# 2025-07-08.net
KiCad netlist of a schematic drawn in EasyEDA Pro
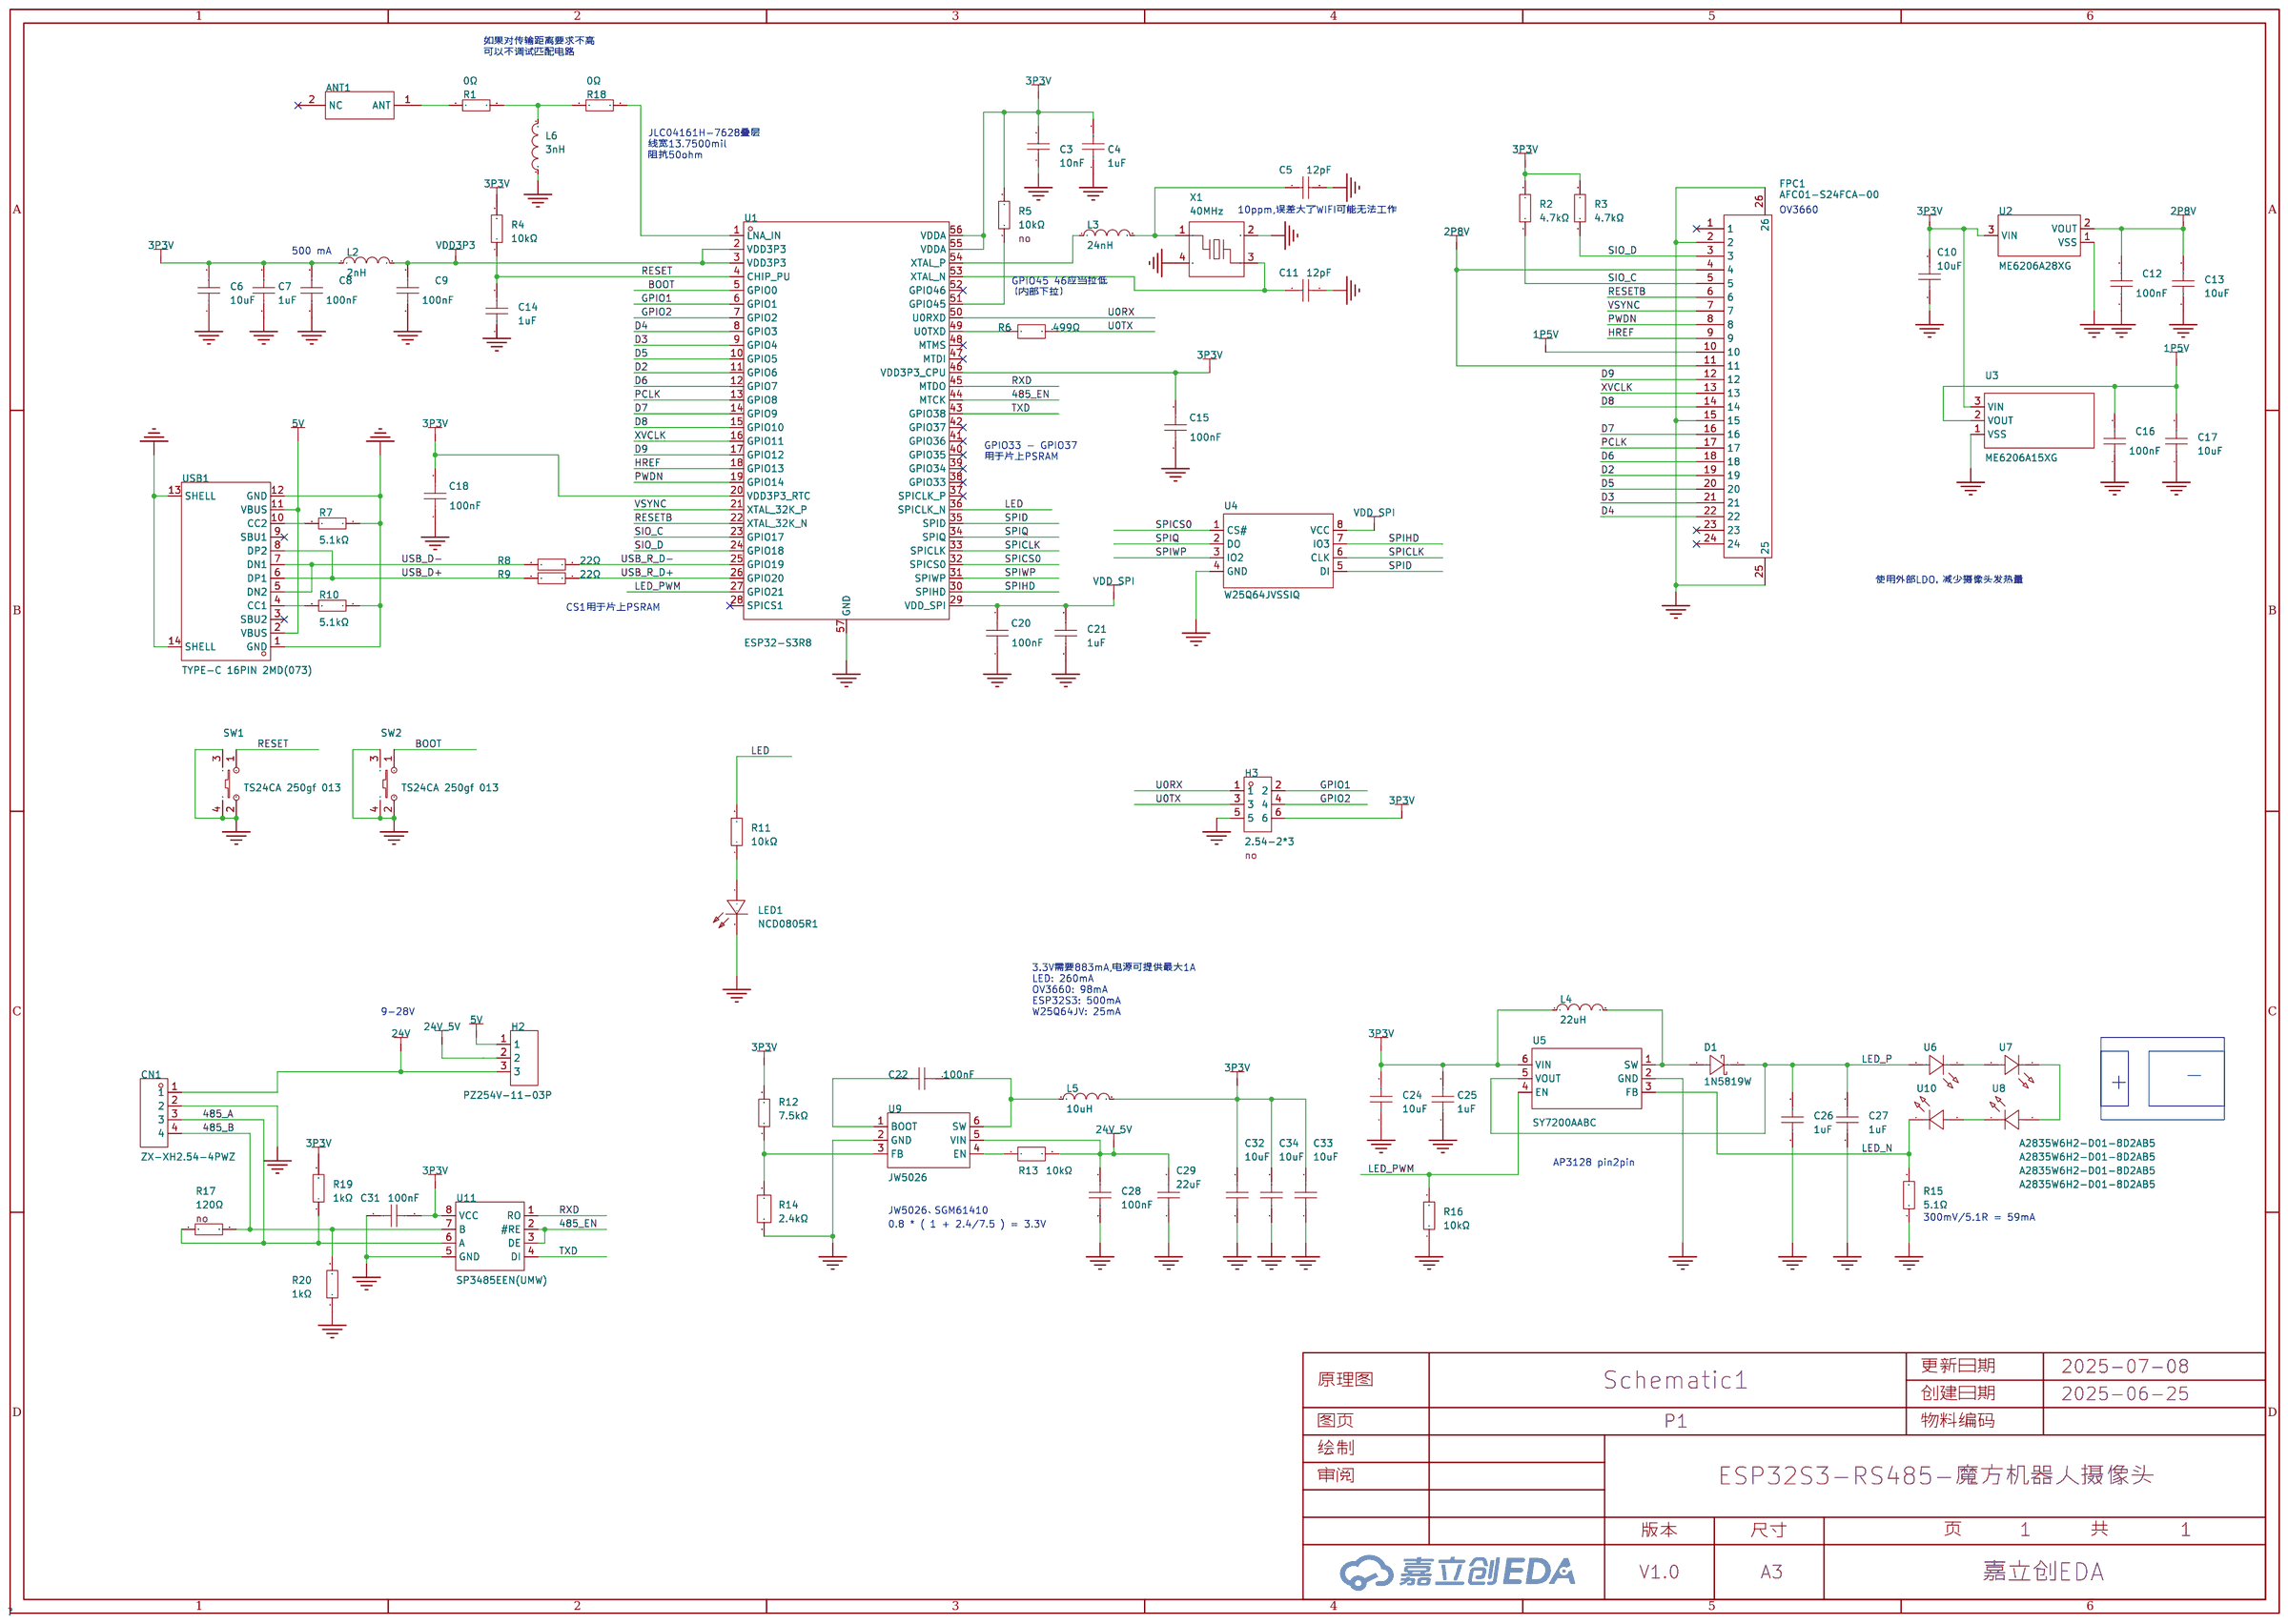
[diagram p0: schematic sheet]

(export (version "E")
  (design (tool "Eeschema 10.0.6"))
  (components
    (comp (ref "ANT1")
      (value "~")
      (footprint "easyedapro:CA-C03")
      (libsource (lib "easyedapro") (part "CA-C03"))
    )
    (comp (ref "C3")
      (value "10nF")
      (footprint "easyedapro:C0603")
      (description "容值:10nF;精度:±10%;额定电压:50V;温度系数:X7R;")
      (fields (field (name "Manufacturer Part") "0603B103K500NT") (field (name "Manufacturer") "FH(风华)"))
      (libsource (lib "easyedapro") (part "0603B103K500NT"))
    )
    (comp (ref "C4")
      (value "1uF")
      (footprint "easyedapro:C0603")
      (description "容值:1uF;精度:±10%;额定电压:50V;材质(温度系数):X5R;")
      (fields
        (field (name "Manufacturer Part") "CL10A105KB8NNNC")
        (field (name "Manufacturer") "SAMSUNG(三星)")
      )
      (libsource (lib "easyedapro") (part "CL10A105KB8NNNC"))
    )
    (comp (ref "C5")
      (value "12pF")
      (footprint "easyedapro:C0603")
      (description "容值:12pF;精度:±5%;额定电压:50V;材质(温度系数):C0G;")
      (fields
        (field (name "Manufacturer Part") "CL10C120JB8NNNC")
        (field (name "Manufacturer") "SAMSUNG(三星)")
      )
      (libsource (lib "easyedapro") (part "CL10C120JB8NNNC"))
    )
    (comp (ref "C6")
      (value "10uF")
      (footprint "easyedapro:C0603")
      (description "容值:10uF;精度:±10%;额定电压:10V;材质(温度系数):X5R;")
      (fields
        (field (name "Manufacturer Part") "CL10A106KP8NNNC")
        (field (name "Manufacturer") "SAMSUNG(三星)")
      )
      (libsource (lib "easyedapro") (part "CL10A106KP8NNNC"))
    )
    (comp (ref "C7")
      (value "1uF")
      (footprint "easyedapro:C0603")
      (description "容值:1uF;精度:±10%;额定电压:50V;材质(温度系数):X5R;")
      (fields
        (field (name "Manufacturer Part") "CL10A105KB8NNNC")
        (field (name "Manufacturer") "SAMSUNG(三星)")
      )
      (libsource (lib "easyedapro") (part "CL10A105KB8NNNC"))
    )
    (comp (ref "C8")
      (value "100nF")
      (footprint "easyedapro:C0603")
      (description "容值:100nF;精度:±10%;额定电压:50V;材质(温度系数):X7R;")
      (fields
        (field (name "Manufacturer Part") "CC0603KRX7R9BB104")
        (field (name "Manufacturer") "YAGEO(国巨)")
      )
      (libsource (lib "easyedapro") (part "CC0603KRX7R9BB104"))
    )
    (comp (ref "C9")
      (value "100nF")
      (footprint "easyedapro:C0603")
      (description "容值:100nF;精度:±10%;额定电压:50V;材质(温度系数):X7R;")
      (fields
        (field (name "Manufacturer Part") "CC0603KRX7R9BB104")
        (field (name "Manufacturer") "YAGEO(国巨)")
      )
      (libsource (lib "easyedapro") (part "CC0603KRX7R9BB104"))
    )
    (comp (ref "C10")
      (value "10uF")
      (footprint "easyedapro:C0603")
      (description "容值:10uF;精度:±10%;额定电压:10V;材质(温度系数):X5R;")
      (fields
        (field (name "Manufacturer Part") "CL10A106KP8NNNC")
        (field (name "Manufacturer") "SAMSUNG(三星)")
      )
      (libsource (lib "easyedapro") (part "CL10A106KP8NNNC"))
    )
    (comp (ref "C11")
      (value "12pF")
      (footprint "easyedapro:C0603")
      (description "容值:12pF;精度:±5%;额定电压:50V;材质(温度系数):C0G;")
      (fields
        (field (name "Manufacturer Part") "CL10C120JB8NNNC")
        (field (name "Manufacturer") "SAMSUNG(三星)")
      )
      (libsource (lib "easyedapro") (part "CL10C120JB8NNNC"))
    )
    (comp (ref "C12")
      (value "100nF")
      (footprint "easyedapro:C0603")
      (description "容值:100nF;精度:±10%;额定电压:50V;材质(温度系数):X7R;")
      (fields
        (field (name "Manufacturer Part") "CC0603KRX7R9BB104")
        (field (name "Manufacturer") "YAGEO(国巨)")
      )
      (libsource (lib "easyedapro") (part "CC0603KRX7R9BB104"))
    )
    (comp (ref "C13")
      (value "10uF")
      (footprint "easyedapro:C0603")
      (description "容值:10uF;精度:±10%;额定电压:10V;材质(温度系数):X5R;")
      (fields
        (field (name "Manufacturer Part") "CL10A106KP8NNNC")
        (field (name "Manufacturer") "SAMSUNG(三星)")
      )
      (libsource (lib "easyedapro") (part "CL10A106KP8NNNC"))
    )
    (comp (ref "C14")
      (value "1uF")
      (footprint "easyedapro:C0603")
      (description "容值:1uF;精度:±10%;额定电压:50V;材质(温度系数):X5R;")
      (fields
        (field (name "Manufacturer Part") "CL10A105KB8NNNC")
        (field (name "Manufacturer") "SAMSUNG(三星)")
      )
      (libsource (lib "easyedapro") (part "CL10A105KB8NNNC"))
    )
    (comp (ref "C15")
      (value "100nF")
      (footprint "easyedapro:C0603")
      (description "容值:100nF;精度:±10%;额定电压:50V;材质(温度系数):X7R;")
      (fields
        (field (name "Manufacturer Part") "CC0603KRX7R9BB104")
        (field (name "Manufacturer") "YAGEO(国巨)")
      )
      (libsource (lib "easyedapro") (part "CC0603KRX7R9BB104"))
    )
    (comp (ref "C16")
      (value "100nF")
      (footprint "easyedapro:C0603")
      (description "容值:100nF;精度:±10%;额定电压:50V;材质(温度系数):X7R;")
      (fields
        (field (name "Manufacturer Part") "CC0603KRX7R9BB104")
        (field (name "Manufacturer") "YAGEO(国巨)")
      )
      (libsource (lib "easyedapro") (part "CC0603KRX7R9BB104"))
    )
    (comp (ref "C17")
      (value "10uF")
      (footprint "easyedapro:C0603")
      (description "容值:10uF;精度:±10%;额定电压:10V;材质(温度系数):X5R;")
      (fields
        (field (name "Manufacturer Part") "CL10A106KP8NNNC")
        (field (name "Manufacturer") "SAMSUNG(三星)")
      )
      (libsource (lib "easyedapro") (part "CL10A106KP8NNNC"))
    )
    (comp (ref "C18")
      (value "100nF")
      (footprint "easyedapro:C0603")
      (description "容值:100nF;精度:±10%;额定电压:50V;材质(温度系数):X7R;")
      (fields
        (field (name "Manufacturer Part") "CC0603KRX7R9BB104")
        (field (name "Manufacturer") "YAGEO(国巨)")
      )
      (libsource (lib "easyedapro") (part "CC0603KRX7R9BB104"))
    )
    (comp (ref "C20")
      (value "100nF")
      (footprint "easyedapro:C0603")
      (description "容值:100nF;精度:±10%;额定电压:50V;材质(温度系数):X7R;")
      (fields
        (field (name "Manufacturer Part") "CC0603KRX7R9BB104")
        (field (name "Manufacturer") "YAGEO(国巨)")
      )
      (libsource (lib "easyedapro") (part "CC0603KRX7R9BB104"))
    )
    (comp (ref "C21")
      (value "1uF")
      (footprint "easyedapro:C0603")
      (description "容值:1uF;精度:±10%;额定电压:50V;材质(温度系数):X5R;")
      (fields
        (field (name "Manufacturer Part") "CL10A105KB8NNNC")
        (field (name "Manufacturer") "SAMSUNG(三星)")
      )
      (libsource (lib "easyedapro") (part "CL10A105KB8NNNC"))
    )
    (comp (ref "C22")
      (value "100nF")
      (footprint "easyedapro:C0603")
      (description "容值:100nF;精度:±10%;额定电压:50V;材质(温度系数):X7R;")
      (fields
        (field (name "Manufacturer Part") "CC0603KRX7R9BB104")
        (field (name "Manufacturer") "YAGEO(国巨)")
      )
      (libsource (lib "easyedapro") (part "CC0603KRX7R9BB104"))
    )
    (comp (ref "C24")
      (value "10uF")
      (footprint "easyedapro:C0603")
      (description "容值:10uF;精度:±10%;额定电压:10V;材质(温度系数):X5R;")
      (fields
        (field (name "Manufacturer Part") "CL10A106KP8NNNC")
        (field (name "Manufacturer") "SAMSUNG(三星)")
      )
      (libsource (lib "easyedapro") (part "CL10A106KP8NNNC"))
    )
    (comp (ref "C25")
      (value "1uF")
      (footprint "easyedapro:C0603")
      (description "容值:1uF;精度:±10%;额定电压:50V;材质(温度系数):X5R;")
      (fields
        (field (name "Manufacturer Part") "CL10A105KB8NNNC")
        (field (name "Manufacturer") "SAMSUNG(三星)")
      )
      (libsource (lib "easyedapro") (part "CL10A105KB8NNNC"))
    )
    (comp (ref "C26")
      (value "1uF")
      (footprint "easyedapro:C0603")
      (description "容值:1uF;精度:±10%;额定电压:50V;材质(温度系数):X5R;")
      (fields
        (field (name "Manufacturer Part") "CL10A105KB8NNNC")
        (field (name "Manufacturer") "SAMSUNG(三星)")
      )
      (libsource (lib "easyedapro") (part "CL10A105KB8NNNC"))
    )
    (comp (ref "C27")
      (value "1uF")
      (footprint "easyedapro:C0603")
      (description "容值:1uF;精度:±10%;额定电压:50V;材质(温度系数):X5R;")
      (fields
        (field (name "Manufacturer Part") "CL10A105KB8NNNC")
        (field (name "Manufacturer") "SAMSUNG(三星)")
      )
      (libsource (lib "easyedapro") (part "CL10A105KB8NNNC"))
    )
    (comp (ref "C28")
      (value "100nF")
      (footprint "easyedapro:C0603")
      (description "容值:100nF;精度:±10%;额定电压:50V;材质(温度系数):X7R;")
      (fields
        (field (name "Manufacturer Part") "CC0603KRX7R9BB104")
        (field (name "Manufacturer") "YAGEO(国巨)")
      )
      (libsource (lib "easyedapro") (part "CC0603KRX7R9BB104"))
    )
    (comp (ref "C29")
      (value "22uF")
      (footprint "easyedapro:C0805")
      (description "容值:22uF;精度:±20%;额定电压:35V;材质(温度系数):X5R;")
      (fields
        (field (name "Manufacturer Part") "CGA0805X5R226M350MT")
        (field (name "Manufacturer") "HRE(芯声)")
      )
      (libsource (lib "easyedapro") (part "CGA0805X5R226M350MT"))
    )
    (comp (ref "C31")
      (value "100nF")
      (footprint "easyedapro:C0603")
      (description "容值:100nF;精度:±10%;额定电压:50V;材质(温度系数):X7R;")
      (fields
        (field (name "Manufacturer Part") "CC0603KRX7R9BB104")
        (field (name "Manufacturer") "YAGEO(国巨)")
      )
      (libsource (lib "easyedapro") (part "CC0603KRX7R9BB104"))
    )
    (comp (ref "C32")
      (value "10uF")
      (footprint "easyedapro:C0603")
      (description "容值:10uF;精度:±10%;额定电压:10V;材质(温度系数):X5R;")
      (fields
        (field (name "Manufacturer Part") "CL10A106KP8NNNC")
        (field (name "Manufacturer") "SAMSUNG(三星)")
      )
      (libsource (lib "easyedapro") (part "CL10A106KP8NNNC"))
    )
    (comp (ref "C33")
      (value "10uF")
      (footprint "easyedapro:C0603")
      (description "容值:10uF;精度:±10%;额定电压:10V;材质(温度系数):X5R;")
      (fields
        (field (name "Manufacturer Part") "CL10A106KP8NNNC")
        (field (name "Manufacturer") "SAMSUNG(三星)")
      )
      (libsource (lib "easyedapro") (part "CL10A106KP8NNNC"))
    )
    (comp (ref "C34")
      (value "10uF")
      (footprint "easyedapro:C0603")
      (description "容值:10uF;精度:±10%;额定电压:10V;材质(温度系数):X5R;")
      (fields
        (field (name "Manufacturer Part") "CL10A106KP8NNNC")
        (field (name "Manufacturer") "SAMSUNG(三星)")
      )
      (libsource (lib "easyedapro") (part "CL10A106KP8NNNC"))
    )
    (comp (ref "CN1")
      (value "ZX-XH2.54-4PWZ")
      (footprint "easyedapro:CONN-TH_4P-P2.50_ZX-XH2.54-4PWZ")
      (fields (field (name "Manufacturer") "Megastar(兆星)"))
      (libsource (lib "easyedapro") (part "ZX-XH2.54-4PWZ"))
    )
    (comp (ref "D1")
      (value "1N5819W")
      (footprint "easyedapro:SOD-123_L2.7-W1.6-LS3.7-RD")
      (description "二极管配置:独立式;正向压降(Vf):600mV@200mA;直流反向耐压(Vr):40V;整流电流:350mA;")
      (fields (field (name "Manufacturer") "JSMSEMI(杰盛微)"))
      (libsource (lib "easyedapro") (part "1N5819W_C963381"))
    )
    (comp (ref "FPC1")
      (value "AFC01-S24FCA-00")
      (footprint "easyedapro:FPC-SMD_24P-P0.50_AFC01-S24FCA-00")
      (description "锁定特性:翻盖式;触点类型:下接;触点数量:24P;间距:0.5mm;安装类型:卧贴;")
      (fields (field (name "Manufacturer") "JS(钜硕电子)"))
      (libsource (lib "easyedapro") (part "AFC01-S24FCA-00"))
    )
    (comp (ref "H2")
      (value "PZ254V-11-03P")
      (footprint "easyedapro:HDR-TH_3P-P2.54-V-M")
      (fields (field (name "Manufacturer") "XFCN(兴飞)"))
      (libsource (lib "easyedapro") (part "PZ254V-11-03P_C2937625"))
    )
    (comp (ref "H3")
      (value "2.54-2*3")
      (footprint "easyedapro:HDR-TH_6P-P2.54-V-R2-C3-S2.54_A2541WV-2X3P")
      (description "插针结构:2x3P;间距:2.54mm;排数:双排;总PIN位数:6P;")
      (fields (field (name "Manufacturer") "ZHOURI(洲日)") (field (name "Add into BOM") "no"))
      (libsource (lib "easyedapro") (part "2.54-2*3"))
    )
    (comp (ref "L2")
      (value "2nH")
      (footprint "easyedapro:L0603")
      (description "电感值:2nH;额定电流:-;饱和电流(Isat):-;直流电阻(DCR):-;")
      (fields
        (field (name "Manufacturer Part") "SDCL1608C2N0STDF")
        (field (name "Manufacturer") "Sunlord(顺络)")
      )
      (libsource (lib "easyedapro") (part "SDCL1608C2N0STDF_C370234"))
    )
    (comp (ref "L3")
      (value "24nH")
      (footprint "easyedapro:IND-SMD_L1.6-W0.8")
      (description "电感值:24nH;精度:±2%;额定电流:500mA;饱和电流(Isat):-;")
      (fields (field (name "Manufacturer Part") "LQW18AN24NG00D") (field (name "Manufacturer") "muRata(村田)"))
      (libsource (lib "easyedapro") (part "LQW18AN24NG00D"))
    )
    (comp (ref "L4")
      (value "22uH")
      (footprint "easyedapro:IND-SMD_L4.0-W4.0")
      (description "电感值:22uH;精度:±20%;额定电流:1.1A;饱和电流(Isat):1.5A;")
      (fields
        (field (name "Manufacturer Part") "FHD4020S-220MT")
        (field (name "Manufacturer") "cjiang(长江微电)")
      )
      (libsource (lib "easyedapro") (part "FHD4020S-220MT"))
    )
    (comp (ref "L5")
      (value "10uH")
      (footprint "easyedapro:IND-SMD_L4.0-W4.0")
      (description "电感值:22uH;精度:±20%;额定电流:1.1A;饱和电流(Isat):1.5A;")
      (fields (field (name "Manufacturer Part") "FNR4030S100MT") (field (name "Manufacturer") "cjiang(长江微电)"))
      (libsource (lib "easyedapro") (part "FHD4020S-220MT"))
    )
    (comp (ref "L6")
      (value "3nH")
      (footprint "easyedapro:L0402")
      (description "电感值:3nH;精度:-;额定电流:800mA;饱和电流(Isat):-;直流电阻(DCR):125mΩ;")
      (fields (field (name "Manufacturer Part") "LQG15HS3N0S02D") (field (name "Manufacturer") "muRata(村田)"))
      (libsource (lib "easyedapro") (part "LQG15HS3N0S02D"))
    )
    (comp (ref "LED1")
      (value "NCD0805R1")
      (footprint "easyedapro:LED0805-R-RD")
      (fields (field (name "Manufacturer") "国星光电"))
      (libsource (lib "easyedapro") (part "FC-2012HRK-620D"))
    )
    (comp (ref "R1")
      (value "0Ω")
      (footprint "easyedapro:R0402")
      (description "电阻类型:厚膜电阻;阻值:0Ω;精度:±1%;功率:62.5mW;最大工作电压:50V;温度系数:±800ppm/°C;")
      (fields
        (field (name "Manufacturer Part") "0402WGF0000TCE")
        (field (name "Manufacturer") "UNI-ROYAL(厚声)")
      )
      (libsource (lib "easyedapro") (part "0402WGF0000TCE"))
    )
    (comp (ref "R2")
      (value "4.7kΩ")
      (footprint "easyedapro:R0603")
      (description "电阻类型:厚膜电阻;阻值:4.7kΩ;精度:±1%;功率:100mW;最大工作电压:75V;温度系数:±100ppm/°C;")
      (fields
        (field (name "Manufacturer Part") "0603WAF4701T5E")
        (field (name "Manufacturer") "UNI-ROYAL(厚声)")
      )
      (libsource (lib "easyedapro") (part "0603WAF4701T5E"))
    )
    (comp (ref "R3")
      (value "4.7kΩ")
      (footprint "easyedapro:R0603")
      (description "电阻类型:厚膜电阻;阻值:4.7kΩ;精度:±1%;功率:100mW;最大工作电压:75V;温度系数:±100ppm/°C;")
      (fields
        (field (name "Manufacturer Part") "0603WAF4701T5E")
        (field (name "Manufacturer") "UNI-ROYAL(厚声)")
      )
      (libsource (lib "easyedapro") (part "0603WAF4701T5E"))
    )
    (comp (ref "R4")
      (value "10kΩ")
      (footprint "easyedapro:R0603")
      (description "电阻类型:厚膜电阻;阻值:10kΩ;精度:±1%;功率:100mW;工作电压:75V;温度系数:±100ppm/°C;")
      (fields
        (field (name "Manufacturer Part") "0603WAF1002T5E")
        (field (name "Manufacturer") "UNI-ROYAL(厚声)")
      )
      (libsource (lib "easyedapro") (part "0603WAF1002T5E"))
    )
    (comp (ref "R5")
      (value "10kΩ")
      (footprint "easyedapro:R0603")
      (description "电阻类型:厚膜电阻;阻值:10kΩ;精度:±1%;功率:100mW;工作电压:75V;温度系数:±100ppm/°C;")
      (fields
        (field (name "Manufacturer Part") "0603WAF1002T5E")
        (field (name "Manufacturer") "UNI-ROYAL(厚声)")
        (field (name "Add into BOM") "no")
      )
      (libsource (lib "easyedapro") (part "0603WAF1002T5E"))
    )
    (comp (ref "R6")
      (value "499Ω")
      (footprint "easyedapro:R0603")
      (description "电阻类型:厚膜电阻;阻值:499Ω;精度:±1%;功率:100mW;工作电压:75V;温度系数:±100ppm/°C;")
      (fields (field (name "Manufacturer Part") "FRC0603F4990TS") (field (name "Manufacturer") "FOJAN(富捷)"))
      (libsource (lib "easyedapro") (part "FRC0603F4990TS"))
    )
    (comp (ref "R7")
      (value "5.1kΩ")
      (footprint "easyedapro:R0603")
      (description "阻值:5.1kΩ;精度:±1%;功率:100mW;温度系数:±100ppm/°C;电阻类型:厚膜电阻;")
      (fields
        (field (name "Manufacturer Part") "0603WAF5101T5E")
        (field (name "Manufacturer") "UNI-ROYAL(厚声)")
      )
      (libsource (lib "easyedapro") (part "0603WAF5101T5E"))
    )
    (comp (ref "R8")
      (value "22Ω")
      (footprint "easyedapro:R0603")
      (description "电阻类型:厚膜电阻;阻值:0Ω;精度:±1%;功率:100mW;最大工作电压:75V;")
      (fields
        (field (name "Manufacturer Part") "0603WAF220JT5E")
        (field (name "Manufacturer") "UNI-ROYAL(厚声)")
      )
      (libsource (lib "easyedapro") (part "0603WAF0000T5E"))
    )
    (comp (ref "R9")
      (value "22Ω")
      (footprint "easyedapro:R0603")
      (description "电阻类型:厚膜电阻;阻值:0Ω;精度:±1%;功率:100mW;最大工作电压:75V;")
      (fields
        (field (name "Manufacturer Part") "0603WAF220JT5E")
        (field (name "Manufacturer") "UNI-ROYAL(厚声)")
      )
      (libsource (lib "easyedapro") (part "0603WAF0000T5E"))
    )
    (comp (ref "R10")
      (value "5.1kΩ")
      (footprint "easyedapro:R0603")
      (description "阻值:5.1kΩ;精度:±1%;功率:100mW;温度系数:±100ppm/°C;电阻类型:厚膜电阻;")
      (fields
        (field (name "Manufacturer Part") "0603WAF5101T5E")
        (field (name "Manufacturer") "UNI-ROYAL(厚声)")
      )
      (libsource (lib "easyedapro") (part "0603WAF5101T5E"))
    )
    (comp (ref "R11")
      (value "10kΩ")
      (footprint "easyedapro:R0603")
      (description "电阻类型:厚膜电阻;阻值:10kΩ;精度:±1%;功率:100mW;工作电压:75V;温度系数:±100ppm/°C;")
      (fields
        (field (name "Manufacturer Part") "0603WAF1002T5E")
        (field (name "Manufacturer") "UNI-ROYAL(厚声)")
      )
      (libsource (lib "easyedapro") (part "0603WAF1002T5E"))
    )
    (comp (ref "R12")
      (value "7.5kΩ")
      (fields
        (field (name "Manufacturer Part") "0603WAF7501T5E")
        (field (name "Manufacturer") "UNI-ROYAL(厚声)")
      )
      (libsource (lib "easyedapro") (part "0603waf4702t5e"))
    )
    (comp (ref "R13")
      (value "10kΩ")
      (footprint "easyedapro:R0603")
      (description "电阻类型:薄膜电阻;阻值:10kΩ;精度:±0.1%;功率:100mW;")
      (fields (field (name "Manufacturer Part") "AT0603BRD0710KL") (field (name "Manufacturer") "YAGEO(国巨)"))
      (libsource (lib "easyedapro") (part "AT0603BRD0710KL"))
    )
    (comp (ref "R14")
      (value "2.4kΩ")
      (fields (field (name "Manufacturer Part") "FRC0603F2401TS") (field (name "Manufacturer") "FOJAN(富捷)"))
      (libsource (lib "easyedapro") (part "FRC0603F1502TS"))
    )
    (comp (ref "R15")
      (value "5.1Ω")
      (footprint "easyedapro:R0603")
      (description "电阻类型:厚膜电阻;阻值:5.1Ω;精度:±1%;功率:100mW;最大工作电压:75V;温度系数:±200ppm/°C;")
      (fields
        (field (name "Manufacturer Part") "0603WAF510KT5E")
        (field (name "Manufacturer") "UNI-ROYAL(厚声)")
      )
      (libsource (lib "easyedapro") (part "0603WAF510KT5E"))
    )
    (comp (ref "R16")
      (value "10kΩ")
      (footprint "easyedapro:R0603")
      (description "电阻类型:厚膜电阻;阻值:10kΩ;精度:±1%;功率:100mW;工作电压:75V;温度系数:±100ppm/°C;")
      (fields
        (field (name "Manufacturer Part") "0603WAF1002T5E")
        (field (name "Manufacturer") "UNI-ROYAL(厚声)")
      )
      (libsource (lib "easyedapro") (part "0603WAF1002T5E"))
    )
    (comp (ref "R17")
      (value "120Ω")
      (footprint "easyedapro:R0603")
      (description "电阻类型:厚膜电阻;阻值:120Ω;精度:±1%;功率:100mW;最大工作电压:75V;温度系数:±100ppm/°C;")
      (fields
        (field (name "Manufacturer Part") "0603WAF1200T5E")
        (field (name "Manufacturer") "UNI-ROYAL(厚声)")
        (field (name "Add into BOM") "no")
      )
      (libsource (lib "easyedapro") (part "0603WAF1200T5E"))
    )
    (comp (ref "R18")
      (value "0Ω")
      (footprint "easyedapro:R0402")
      (description "电阻类型:厚膜电阻;阻值:0Ω;精度:±1%;功率:62.5mW;最大工作电压:50V;温度系数:±800ppm/°C;")
      (fields
        (field (name "Manufacturer Part") "0402WGF0000TCE")
        (field (name "Manufacturer") "UNI-ROYAL(厚声)")
      )
      (libsource (lib "easyedapro") (part "0402WGF0000TCE"))
    )
    (comp (ref "R19")
      (value "1kΩ")
      (footprint "easyedapro:R0603")
      (description "电阻类型:厚膜电阻;阻值:1kΩ;精度:±1%;功率:100mW;最大工作电压:75V;温度系数:±100ppm/°C;")
      (fields
        (field (name "Manufacturer Part") "0603WAF1001T5E")
        (field (name "Manufacturer") "UNI-ROYAL(厚声)")
      )
      (libsource (lib "easyedapro") (part "0603WAF1001T5E"))
    )
    (comp (ref "R20")
      (value "1kΩ")
      (footprint "easyedapro:R0603")
      (description "电阻类型:厚膜电阻;阻值:1kΩ;精度:±1%;功率:100mW;最大工作电压:75V;温度系数:±100ppm/°C;")
      (fields
        (field (name "Manufacturer Part") "0603WAF1001T5E")
        (field (name "Manufacturer") "UNI-ROYAL(厚声)")
      )
      (libsource (lib "easyedapro") (part "0603WAF1001T5E"))
    )
    (comp (ref "SW1")
      (value "TS24CA 250gf 013")
      (footprint "easyedapro:SW-SMD_L4.7-W3.5-P3.35-EH")
      (fields (field (name "Manufacturer") "SHOU HAN(首韩)"))
      (libsource (lib "easyedapro") (part "TS24CA 250GF 013"))
    )
    (comp (ref "SW2")
      (value "TS24CA 250gf 013")
      (footprint "easyedapro:SW-SMD_L4.7-W3.5-P3.35-EH")
      (fields (field (name "Manufacturer") "SHOU HAN(首韩)"))
      (libsource (lib "easyedapro") (part "TS24CA 250GF 013"))
    )
    (comp (ref "U1")
      (value "ESP32-S3R8")
      (footprint "easyedapro:QFN-56_L7.0-W7.0-P0.40-TL-EP4.0")
      (fields (field (name "Manufacturer") "ESPRESSIF(乐鑫)"))
      (libsource (lib "easyedapro") (part "ESP32-S3(R8)"))
    )
    (comp (ref "U2")
      (value "ME6206A28XG")
      (footprint "easyedapro:SOT-23_L2.9-W1.3-P1.90-LS2.4-BR")
      (description "输出类型:固定;工作电压:6V;输出电压:2.8V;输出电流:300mA;电源纹波抑制比(PSRR):50dB@(1kHz);输出极性:正极;")
      (fields (field (name "Manufacturer") "MICRONE(南京微盟)"))
      (libsource (lib "easyedapro") (part "ME6206A28XG"))
    )
    (comp (ref "U3")
      (value "ME6206A15XG")
      (footprint "easyedapro:SOT-23-3_L2.9-W1.6-P1.90-LS2.8-BR")
      (description "输出类型:固定;工作电压:6V;输出电压:1.5V;输出电流:100mA;电源纹波抑制比(PSRR):45dB@(1kHz);输出极性:正极;")
      (fields (field (name "Manufacturer") "MICRONE(南京微盟)"))
      (libsource (lib "easyedapro") (part "ME6206A15XG"))
    )
    (comp (ref "U4")
      (value "W25Q64JVSSIQ")
      (footprint "easyedapro:SOP-8_L5.3-W5.3-P1.27-LS8.0-BL")
      (description "接口类型:SPI;存储容量:-;时钟频率(fc):133MHz;")
      (fields (field (name "Manufacturer") "WINBOND(华邦)"))
      (libsource (lib "easyedapro") (part "W25Q64JVSSIQ"))
    )
    (comp (ref "U5")
      (value "SY7200AABC")
      (footprint "easyedapro:SOT-23-6_L2.9-W1.6-P0.95-LS2.8-BR")
      (description "类型:-;工作电压:2.5V~5.5V;开关频率:-;通道数:-;输出电压:-;调光:-;拓扑结构:升压;")
      (fields (field (name "Manufacturer") "silergy(矽力杰)"))
      (libsource (lib "easyedapro") (part "AP3128AE3036ES6"))
    )
    (comp (ref "U6")
      (value "A2835W6H2-D01-8D2AB5")
      (footprint "easyedapro:LED-SMD_L3.5-W2.8-FD-2835_WHITE")
      (description "发光颜色:白色;正向电压(VF):2.9V~3.3V;正向电流:-;色温:6500K;")
      (fields (field (name "Manufacturer") "HONGLITRONIC(鸿利光电)"))
      (libsource (lib "easyedapro") (part "A2835W6H2-D01-8D2AB5"))
    )
    (comp (ref "U7")
      (value "A2835W6H2-D01-8D2AB5")
      (footprint "easyedapro:LED-SMD_L3.5-W2.8-FD-2835_WHITE")
      (description "发光颜色:白色;正向电压(VF):2.9V~3.3V;正向电流:-;色温:6500K;")
      (fields (field (name "Manufacturer") "HONGLITRONIC(鸿利光电)"))
      (libsource (lib "easyedapro") (part "A2835W6H2-D01-8D2AB5"))
    )
    (comp (ref "U8")
      (value "A2835W6H2-D01-8D2AB5")
      (footprint "easyedapro:LED-SMD_L3.5-W2.8-FD-2835_WHITE")
      (description "发光颜色:白色;正向电压(VF):2.9V~3.3V;正向电流:-;色温:6500K;")
      (fields (field (name "Manufacturer") "HONGLITRONIC(鸿利光电)"))
      (libsource (lib "easyedapro") (part "A2835W6H2-D01-8D2AB5"))
    )
    (comp (ref "U9")
      (value "JW5026")
      (footprint "easyedapro:TSOT-23-6_L2.9-W1.6-P0.95-LS2.8-BL")
      (fields (field (name "Manufacturer") "Joulwatt(杰华特)"))
      (libsource (lib "easyedapro") (part "SGM61410XN6G/TR"))
    )
    (comp (ref "U10")
      (value "A2835W6H2-D01-8D2AB5")
      (footprint "easyedapro:LED-SMD_L3.5-W2.8-FD-2835_WHITE")
      (description "发光颜色:白色;正向电压(VF):2.9V~3.3V;正向电流:-;色温:6500K;")
      (fields (field (name "Manufacturer") "HONGLITRONIC(鸿利光电)"))
      (libsource (lib "easyedapro") (part "A2835W6H2-D01-8D2AB5"))
    )
    (comp (ref "U11")
      (value "SP3485EEN(UMW)")
      (footprint "easyedapro:SOP-8_L5.0-W4.0-P1.27-LS6.0-BL")
      (description "类型:收发器;数据速率:12Mbps;")
      (fields (field (name "Manufacturer") "UMW(友台半导体)"))
      (libsource (lib "easyedapro") (part "SP3485EEN"))
    )
    (comp (ref "USB1")
      (value "TYPE-C 16PIN 2MD(073)")
      (footprint "easyedapro:USB-C-SMD_TYPE-C-6PIN-2MD-073")
      (description "连接器类型:Type-C;标准:-;公母:母;触点数量:16P;端口数量:1;安装方式:卧贴;额定电流 - 电源:5A;工作温度范围:-25°C~+85°C;")
      (fields (field (name "Manufacturer") "SHOU HAN(首韩)"))
      (libsource (lib "easyedapro") (part "TYPE-C 16PIN 2MD(073)"))
    )
    (comp (ref "X1")
      (value "40MHz")
      (footprint "easyedapro:CRYSTAL-SMD_4P-L3.2-W2.5-BL_SIT8008BI")
      (description "晶振类型:贴片晶振;频率:40MHz;常温频差:±10ppm;负载电容:10pF;频率稳定度:±30ppm;")
      (fields (field (name "Manufacturer Part") "CF4040M00010001") (field (name "Manufacturer") "HUAXIN(华昕)"))
      (libsource (lib "easyedapro") (part "CF4040M00010001"))
    )
  )
  (nets
    (net (code "1") (name "/485_A") (class "Default")
      (node (ref "CN1") (pin "3") (pinfunction "3_3") (pintype "unspecified"))
      (node (ref "R17") (pin "1") (pinfunction "1_1") (pintype "input"))
      (node (ref "R19") (pin "1") (pinfunction "1_1") (pintype "input"))
      (node (ref "U11") (pin "6") (pinfunction "A_6") (pintype "unspecified"))
    )
    (net (code "2") (name "/485_B") (class "Default")
      (node (ref "CN1") (pin "4") (pinfunction "4_4") (pintype "unspecified"))
      (node (ref "R17") (pin "2") (pinfunction "2_2") (pintype "input"))
      (node (ref "R20") (pin "2") (pinfunction "2_2") (pintype "input"))
      (node (ref "U11") (pin "7") (pinfunction "B_7") (pintype "unspecified"))
    )
    (net (code "3") (name "/485_EN") (class "Default")
      (node (ref "U1") (pin "44") (pinfunction "MTCK_44") (pintype "unspecified"))
      (node (ref "U11") (pin "2") (pinfunction "#RE_2") (pintype "unspecified"))
      (node (ref "U11") (pin "3") (pinfunction "DE_3") (pintype "unspecified"))
    )
    (net (code "4") (name "/BOOT") (class "Default")
      (node (ref "SW2") (pin "1") (pinfunction "1_1") (pintype "unspecified"))
      (node (ref "U1") (pin "5") (pinfunction "GPIO0_5") (pintype "unspecified"))
    )
    (net (code "5") (name "/D2") (class "Default")
      (node (ref "FPC1") (pin "19") (pinfunction "19_19") (pintype "unspecified"))
      (node (ref "U1") (pin "11") (pinfunction "GPIO6_11") (pintype "unspecified"))
    )
    (net (code "6") (name "/D3") (class "Default")
      (node (ref "FPC1") (pin "21") (pinfunction "21_21") (pintype "unspecified"))
      (node (ref "U1") (pin "9") (pinfunction "GPIO4_9") (pintype "unspecified"))
    )
    (net (code "7") (name "/D4") (class "Default")
      (node (ref "FPC1") (pin "22") (pinfunction "22_22") (pintype "unspecified"))
      (node (ref "U1") (pin "8") (pinfunction "GPIO3_8") (pintype "unspecified"))
    )
    (net (code "8") (name "/D5") (class "Default")
      (node (ref "FPC1") (pin "20") (pinfunction "20_20") (pintype "unspecified"))
      (node (ref "U1") (pin "10") (pinfunction "GPIO5_10") (pintype "unspecified"))
    )
    (net (code "9") (name "/D6") (class "Default")
      (node (ref "FPC1") (pin "18") (pinfunction "18_18") (pintype "unspecified"))
      (node (ref "U1") (pin "12") (pinfunction "GPIO7_12") (pintype "unspecified"))
    )
    (net (code "10") (name "/D7") (class "Default")
      (node (ref "FPC1") (pin "16") (pinfunction "16_16") (pintype "unspecified"))
      (node (ref "U1") (pin "14") (pinfunction "GPIO9_14") (pintype "unspecified"))
    )
    (net (code "11") (name "/D8") (class "Default")
      (node (ref "FPC1") (pin "14") (pinfunction "14_14") (pintype "unspecified"))
      (node (ref "U1") (pin "15") (pinfunction "GPIO10_15") (pintype "unspecified"))
    )
    (net (code "12") (name "/D9") (class "Default")
      (node (ref "FPC1") (pin "12") (pinfunction "12_12") (pintype "unspecified"))
      (node (ref "U1") (pin "17") (pinfunction "GPIO12_17") (pintype "unspecified"))
    )
    (net (code "13") (name "/GPIO1") (class "Default")
      (node (ref "H3") (pin "2") (pinfunction "2_2") (pintype "unspecified"))
      (node (ref "U1") (pin "6") (pinfunction "GPIO1_6") (pintype "unspecified"))
    )
    (net (code "14") (name "/GPIO2") (class "Default")
      (node (ref "H3") (pin "4") (pinfunction "4_4") (pintype "unspecified"))
      (node (ref "U1") (pin "7") (pinfunction "GPIO2_7") (pintype "unspecified"))
    )
    (net (code "15") (name "/HREF") (class "Default")
      (node (ref "FPC1") (pin "9") (pinfunction "9_9") (pintype "unspecified"))
      (node (ref "U1") (pin "18") (pinfunction "GPIO13_18") (pintype "unspecified"))
    )
    (net (code "16") (name "/LED") (class "Default")
      (node (ref "R11") (pin "2") (pinfunction "2_2") (pintype "input"))
      (node (ref "U1") (pin "36") (pinfunction "SPICLK_N_36") (pintype "unspecified"))
    )
    (net (code "17") (name "/LED_N") (class "Default")
      (node (ref "R15") (pin "2") (pinfunction "2_2") (pintype "input"))
      (node (ref "U10") (pin "1") (pinfunction "K_1") (pintype "unspecified"))
      (node (ref "U5") (pin "3") (pinfunction "FB_3") (pintype "unspecified"))
    )
    (net (code "18") (name "/LED_P") (class "Default")
      (node (ref "C26") (pin "2") (pinfunction "2_2") (pintype "unspecified"))
      (node (ref "C27") (pin "2") (pinfunction "2_2") (pintype "unspecified"))
      (node (ref "D1") (pin "1") (pinfunction "C_1") (pintype "unspecified"))
      (node (ref "U5") (pin "5") (pinfunction "VOUT_5") (pintype "unspecified"))
      (node (ref "U6") (pin "2") (pinfunction "A_2") (pintype "unspecified"))
    )
    (net (code "19") (name "/LED_PWM") (class "Default")
      (node (ref "R16") (pin "2") (pinfunction "2_2") (pintype "input"))
      (node (ref "U1") (pin "27") (pinfunction "GPIO21_27") (pintype "unspecified"))
      (node (ref "U5") (pin "4") (pinfunction "EN_4") (pintype "unspecified"))
    )
    (net (code "20") (name "/PCLK") (class "Default")
      (node (ref "FPC1") (pin "17") (pinfunction "17_17") (pintype "unspecified"))
      (node (ref "U1") (pin "13") (pinfunction "GPIO8_13") (pintype "unspecified"))
    )
    (net (code "21") (name "/PWDN") (class "Default")
      (node (ref "FPC1") (pin "8") (pinfunction "8_8") (pintype "unspecified"))
      (node (ref "U1") (pin "19") (pinfunction "GPIO14_19") (pintype "unspecified"))
    )
    (net (code "22") (name "/RESET") (class "Default")
      (node (ref "C14") (pin "2") (pinfunction "2_2") (pintype "unspecified"))
      (node (ref "R4") (pin "1") (pinfunction "1_1") (pintype "input"))
      (node (ref "SW1") (pin "1") (pinfunction "1_1") (pintype "unspecified"))
      (node (ref "U1") (pin "4") (pinfunction "CHIP_PU_4") (pintype "unspecified"))
    )
    (net (code "23") (name "/RESETB") (class "Default")
      (node (ref "FPC1") (pin "6") (pinfunction "6_6") (pintype "unspecified"))
      (node (ref "U1") (pin "22") (pinfunction "XTAL_32K_N_22") (pintype "unspecified"))
    )
    (net (code "24") (name "/RXD") (class "Default")
      (node (ref "U1") (pin "45") (pinfunction "MTDO_45") (pintype "unspecified"))
      (node (ref "U11") (pin "1") (pinfunction "RO_1") (pintype "unspecified"))
    )
    (net (code "25") (name "/SIO_C") (class "Default")
      (node (ref "FPC1") (pin "5") (pinfunction "5_5") (pintype "unspecified"))
      (node (ref "R2") (pin "1") (pinfunction "1_1") (pintype "input"))
      (node (ref "U1") (pin "23") (pinfunction "GPIO17_23") (pintype "unspecified"))
    )
    (net (code "26") (name "/SIO_D") (class "Default")
      (node (ref "FPC1") (pin "3") (pinfunction "3_3") (pintype "unspecified"))
      (node (ref "R3") (pin "1") (pinfunction "1_1") (pintype "input"))
      (node (ref "U1") (pin "24") (pinfunction "GPIO18_24") (pintype "unspecified"))
    )
    (net (code "27") (name "/SPICLK") (class "Default")
      (node (ref "U1") (pin "33") (pinfunction "SPICLK_33") (pintype "unspecified"))
      (node (ref "U4") (pin "6") (pinfunction "CLK_6") (pintype "unspecified"))
    )
    (net (code "28") (name "/SPICS0") (class "Default")
      (node (ref "U1") (pin "32") (pinfunction "SPICS0_32") (pintype "unspecified"))
      (node (ref "U4") (pin "1") (pinfunction "CS#_1") (pintype "unspecified"))
    )
    (net (code "29") (name "/SPID") (class "Default")
      (node (ref "U1") (pin "35") (pinfunction "SPID_35") (pintype "unspecified"))
      (node (ref "U4") (pin "5") (pinfunction "DI_5") (pintype "unspecified"))
    )
    (net (code "30") (name "/SPIHD") (class "Default")
      (node (ref "U1") (pin "30") (pinfunction "SPIHD_30") (pintype "unspecified"))
      (node (ref "U4") (pin "7") (pinfunction "IO3_7") (pintype "unspecified"))
    )
    (net (code "31") (name "/SPIQ") (class "Default")
      (node (ref "U1") (pin "34") (pinfunction "SPIQ_34") (pintype "unspecified"))
      (node (ref "U4") (pin "2") (pinfunction "DO_2") (pintype "unspecified"))
    )
    (net (code "32") (name "/SPIWP") (class "Default")
      (node (ref "U1") (pin "31") (pinfunction "SPIWP_31") (pintype "unspecified"))
      (node (ref "U4") (pin "3") (pinfunction "IO2_3") (pintype "unspecified"))
    )
    (net (code "33") (name "/TXD") (class "Default")
      (node (ref "U1") (pin "43") (pinfunction "GPIO38_43") (pintype "unspecified"))
      (node (ref "U11") (pin "4") (pinfunction "DI_4") (pintype "unspecified"))
    )
    (net (code "34") (name "/U0RX") (class "Default")
      (node (ref "H3") (pin "1") (pinfunction "1_1") (pintype "unspecified"))
      (node (ref "U1") (pin "50") (pinfunction "U0RXD_50") (pintype "unspecified"))
    )
    (net (code "35") (name "/U0TX") (class "Default")
      (node (ref "H3") (pin "3") (pinfunction "3_3") (pintype "unspecified"))
      (node (ref "R6") (pin "2") (pinfunction "2_2") (pintype "unspecified"))
    )
    (net (code "36") (name "/USB_D+") (class "Default")
      (node (ref "R9") (pin "1") (pinfunction "1_1") (pintype "input"))
      (node (ref "USB1") (pin "6") (pinfunction "DP1_6") (pintype "unspecified"))
      (node (ref "USB1") (pin "8") (pinfunction "DP2_8") (pintype "unspecified"))
    )
    (net (code "37") (name "/USB_D-") (class "Default")
      (node (ref "R8") (pin "1") (pinfunction "1_1") (pintype "input"))
      (node (ref "USB1") (pin "5") (pinfunction "DN2_5") (pintype "unspecified"))
      (node (ref "USB1") (pin "7") (pinfunction "DN1_7") (pintype "unspecified"))
    )
    (net (code "38") (name "/USB_R_D+") (class "Default")
      (node (ref "R9") (pin "2") (pinfunction "2_2") (pintype "input"))
      (node (ref "U1") (pin "26") (pinfunction "GPIO20_26") (pintype "unspecified"))
    )
    (net (code "39") (name "/USB_R_D-") (class "Default")
      (node (ref "R8") (pin "2") (pinfunction "2_2") (pintype "input"))
      (node (ref "U1") (pin "25") (pinfunction "GPIO19_25") (pintype "unspecified"))
    )
    (net (code "40") (name "/VSYNC") (class "Default")
      (node (ref "FPC1") (pin "7") (pinfunction "7_7") (pintype "unspecified"))
      (node (ref "U1") (pin "21") (pinfunction "XTAL_32K_P_21") (pintype "unspecified"))
    )
    (net (code "41") (name "/XVCLK") (class "Default")
      (node (ref "FPC1") (pin "13") (pinfunction "13_13") (pintype "unspecified"))
      (node (ref "U1") (pin "16") (pinfunction "GPIO11_16") (pintype "unspecified"))
    )
    (net (code "42") (name "1P5V") (class "Default")
      (node (ref "C16") (pin "2") (pinfunction "2_2") (pintype "unspecified"))
      (node (ref "C17") (pin "2") (pinfunction "2_2") (pintype "unspecified"))
      (node (ref "FPC1") (pin "10") (pinfunction "10_10") (pintype "unspecified"))
      (node (ref "U3") (pin "2") (pinfunction "VOUT_2") (pintype "unspecified"))
    )
    (net (code "43") (name "2P8V") (class "Default")
      (node (ref "C12") (pin "2") (pinfunction "2_2") (pintype "unspecified"))
      (node (ref "C13") (pin "2") (pinfunction "2_2") (pintype "unspecified"))
      (node (ref "FPC1") (pin "11") (pinfunction "11_11") (pintype "unspecified"))
      (node (ref "FPC1") (pin "4") (pinfunction "4_4") (pintype "unspecified"))
      (node (ref "U2") (pin "2") (pinfunction "VOUT_2") (pintype "unspecified"))
    )
    (net (code "44") (name "3P3V") (class "Default")
      (node (ref "C10") (pin "2") (pinfunction "2_2") (pintype "unspecified"))
      (node (ref "C15") (pin "2") (pinfunction "2_2") (pintype "unspecified"))
      (node (ref "C18") (pin "2") (pinfunction "2_2") (pintype "unspecified"))
      (node (ref "C24") (pin "2") (pinfunction "2_2") (pintype "unspecified"))
      (node (ref "C25") (pin "2") (pinfunction "2_2") (pintype "unspecified"))
      (node (ref "C3") (pin "2") (pinfunction "2_2") (pintype "input"))
      (node (ref "C31") (pin "1") (pinfunction "1_1") (pintype "unspecified"))
      (node (ref "C32") (pin "2") (pinfunction "2_2") (pintype "unspecified"))
      (node (ref "C33") (pin "2") (pinfunction "2_2") (pintype "unspecified"))
      (node (ref "C34") (pin "2") (pinfunction "2_2") (pintype "unspecified"))
      (node (ref "C4") (pin "2") (pinfunction "2_2") (pintype "unspecified"))
      (node (ref "C6") (pin "2") (pinfunction "2_2") (pintype "unspecified"))
      (node (ref "C7") (pin "2") (pinfunction "2_2") (pintype "unspecified"))
      (node (ref "C8") (pin "2") (pinfunction "2_2") (pintype "unspecified"))
      (node (ref "H3") (pin "6") (pinfunction "6_6") (pintype "unspecified"))
      (node (ref "L2") (pin "1") (pinfunction "1_1") (pintype "unspecified"))
      (node (ref "L4") (pin "1") (pinfunction "1_1") (pintype "unspecified"))
      (node (ref "L5") (pin "2") (pinfunction "2_2") (pintype "unspecified"))
      (node (ref "R12") (pin "2") (pinfunction "2_2") (pintype "input"))
      (node (ref "R19") (pin "2") (pinfunction "2_2") (pintype "input"))
      (node (ref "R2") (pin "2") (pinfunction "2_2") (pintype "input"))
      (node (ref "R3") (pin "2") (pinfunction "2_2") (pintype "input"))
      (node (ref "R4") (pin "2") (pinfunction "2_2") (pintype "input"))
      (node (ref "R5") (pin "2") (pinfunction "2_2") (pintype "input"))
      (node (ref "U1") (pin "20") (pinfunction "VDD3P3_RTC_20") (pintype "unspecified"))
      (node (ref "U1") (pin "46") (pinfunction "VDD3P3_CPU_46") (pintype "unspecified"))
      (node (ref "U1") (pin "55") (pinfunction "VDDA_55") (pintype "unspecified"))
      (node (ref "U1") (pin "56") (pinfunction "VDDA_56") (pintype "unspecified"))
      (node (ref "U11") (pin "8") (pinfunction "VCC_8") (pintype "unspecified"))
      (node (ref "U2") (pin "3") (pinfunction "VIN_3") (pintype "unspecified"))
      (node (ref "U3") (pin "3") (pinfunction "VIN_3") (pintype "unspecified"))
      (node (ref "U5") (pin "6") (pinfunction "VIN_6") (pintype "unspecified"))
    )
    (net (code "45") (name "5V") (class "Default")
      (node (ref "H2") (pin "1") (pinfunction "1_1") (pintype "unspecified"))
      (node (ref "USB1") (pin "11") (pinfunction "VBUS_11") (pintype "unspecified"))
      (node (ref "USB1") (pin "2") (pinfunction "VBUS_2") (pintype "unspecified"))
    )
    (net (code "46") (name "24V") (class "Default")
      (node (ref "CN1") (pin "1") (pinfunction "1_1") (pintype "unspecified"))
      (node (ref "H2") (pin "3") (pinfunction "3_3") (pintype "unspecified"))
    )
    (net (code "47") (name "24V_5V") (class "Default")
      (node (ref "C28") (pin "1") (pinfunction "1_1") (pintype "unspecified"))
      (node (ref "C29") (pin "2") (pinfunction "2_2") (pintype "unspecified"))
      (node (ref "H2") (pin "2") (pinfunction "2_2") (pintype "unspecified"))
      (node (ref "R13") (pin "2") (pinfunction "2_2") (pintype "unspecified"))
      (node (ref "U9") (pin "5") (pinfunction "VIN_5") (pintype "unspecified"))
    )
    (net (code "48") (name "GND") (class "Default")
      (node (ref "C10") (pin "1") (pinfunction "1_1") (pintype "unspecified"))
      (node (ref "C11") (pin "1") (pinfunction "1_1") (pintype "input"))
      (node (ref "C12") (pin "1") (pinfunction "1_1") (pintype "unspecified"))
      (node (ref "C13") (pin "1") (pinfunction "1_1") (pintype "unspecified"))
      (node (ref "C14") (pin "1") (pinfunction "1_1") (pintype "unspecified"))
      (node (ref "C15") (pin "1") (pinfunction "1_1") (pintype "unspecified"))
      (node (ref "C16") (pin "1") (pinfunction "1_1") (pintype "unspecified"))
      (node (ref "C17") (pin "1") (pinfunction "1_1") (pintype "unspecified"))
      (node (ref "C18") (pin "1") (pinfunction "1_1") (pintype "unspecified"))
      (node (ref "C20") (pin "1") (pinfunction "1_1") (pintype "unspecified"))
      (node (ref "C21") (pin "1") (pinfunction "1_1") (pintype "unspecified"))
      (node (ref "C24") (pin "1") (pinfunction "1_1") (pintype "unspecified"))
      (node (ref "C25") (pin "1") (pinfunction "1_1") (pintype "unspecified"))
      (node (ref "C26") (pin "1") (pinfunction "1_1") (pintype "unspecified"))
      (node (ref "C27") (pin "1") (pinfunction "1_1") (pintype "unspecified"))
      (node (ref "C28") (pin "2") (pinfunction "2_2") (pintype "unspecified"))
      (node (ref "C29") (pin "1") (pinfunction "1_1") (pintype "unspecified"))
      (node (ref "C3") (pin "1") (pinfunction "1_1") (pintype "input"))
      (node (ref "C31") (pin "2") (pinfunction "2_2") (pintype "unspecified"))
      (node (ref "C32") (pin "1") (pinfunction "1_1") (pintype "unspecified"))
      (node (ref "C33") (pin "1") (pinfunction "1_1") (pintype "unspecified"))
      (node (ref "C34") (pin "1") (pinfunction "1_1") (pintype "unspecified"))
      (node (ref "C4") (pin "1") (pinfunction "1_1") (pintype "unspecified"))
      (node (ref "C5") (pin "2") (pinfunction "2_2") (pintype "input"))
      (node (ref "C6") (pin "1") (pinfunction "1_1") (pintype "unspecified"))
      (node (ref "C7") (pin "1") (pinfunction "1_1") (pintype "unspecified"))
      (node (ref "C8") (pin "1") (pinfunction "1_1") (pintype "unspecified"))
      (node (ref "C9") (pin "1") (pinfunction "1_1") (pintype "unspecified"))
      (node (ref "CN1") (pin "2") (pinfunction "2_2") (pintype "unspecified"))
      (node (ref "FPC1") (pin "15") (pinfunction "15_15") (pintype "unspecified"))
      (node (ref "FPC1") (pin "2") (pinfunction "2_2") (pintype "unspecified"))
      (node (ref "FPC1") (pin "25") (pinfunction "25_25") (pintype "unspecified"))
      (node (ref "FPC1") (pin "26") (pinfunction "26_26") (pintype "unspecified"))
      (node (ref "H3") (pin "5") (pinfunction "5_5") (pintype "unspecified"))
      (node (ref "L6") (pin "1") (pinfunction "1_1") (pintype "unspecified"))
      (node (ref "LED1") (pin "2") (pinfunction "-_2") (pintype "unspecified"))
      (node (ref "R10") (pin "1") (pinfunction "1_1") (pintype "input"))
      (node (ref "R14") (pin "1") (pinfunction "1_1") (pintype "unspecified"))
      (node (ref "R15") (pin "1") (pinfunction "1_1") (pintype "input"))
      (node (ref "R16") (pin "1") (pinfunction "1_1") (pintype "input"))
      (node (ref "R20") (pin "1") (pinfunction "1_1") (pintype "input"))
      (node (ref "R7") (pin "1") (pinfunction "1_1") (pintype "input"))
      (node (ref "SW1") (pin "2") (pinfunction "2_2") (pintype "unspecified"))
      (node (ref "SW1") (pin "3") (pinfunction "3_3") (pintype "unspecified"))
      (node (ref "SW1") (pin "4") (pinfunction "4_4") (pintype "unspecified"))
      (node (ref "SW2") (pin "2") (pinfunction "2_2") (pintype "unspecified"))
      (node (ref "SW2") (pin "3") (pinfunction "3_3") (pintype "unspecified"))
      (node (ref "SW2") (pin "4") (pinfunction "4_4") (pintype "unspecified"))
      (node (ref "U1") (pin "57") (pinfunction "GND_57") (pintype "unspecified"))
      (node (ref "U11") (pin "5") (pinfunction "GND_5") (pintype "unspecified"))
      (node (ref "U2") (pin "1") (pinfunction "VSS_1") (pintype "unspecified"))
      (node (ref "U3") (pin "1") (pinfunction "VSS_1") (pintype "unspecified"))
      (node (ref "U4") (pin "4") (pinfunction "GND_4") (pintype "unspecified"))
      (node (ref "U5") (pin "2") (pinfunction "GND_2") (pintype "unspecified"))
      (node (ref "U9") (pin "2") (pinfunction "GND_2") (pintype "unspecified"))
      (node (ref "USB1") (pin "1") (pinfunction "GND_1") (pintype "unspecified"))
      (node (ref "USB1") (pin "12") (pinfunction "GND_12") (pintype "unspecified"))
      (node (ref "USB1") (pin "13") (pinfunction "SHELL_13") (pintype "unspecified"))
      (node (ref "USB1") (pin "14") (pinfunction "SHELL_14") (pintype "unspecified"))
      (node (ref "X1") (pin "2") (pinfunction "GND_2") (pintype "input"))
      (node (ref "X1") (pin "4") (pinfunction "GND_4") (pintype "input"))
    )
    (net (code "49") (name "Net-(ANT1-ANT)") (class "Default")
      (node (ref "ANT1") (pin "1") (pinfunction "ANT_1") (pintype "input"))
      (node (ref "R1") (pin "1") (pinfunction "1_1") (pintype "input"))
    )
    (net (code "50") (name "Net-(C5-Pad1)") (class "Default")
      (node (ref "C5") (pin "1") (pinfunction "1_1") (pintype "input"))
      (node (ref "L3") (pin "2") (pinfunction "2_2") (pintype "unspecified"))
      (node (ref "X1") (pin "1") (pinfunction "1_1") (pintype "input"))
    )
    (net (code "51") (name "Net-(D1-A)") (class "Default")
      (node (ref "D1") (pin "2") (pinfunction "A_2") (pintype "unspecified"))
      (node (ref "L4") (pin "2") (pinfunction "2_2") (pintype "unspecified"))
      (node (ref "U5") (pin "1") (pinfunction "SW_1") (pintype "unspecified"))
    )
    (net (code "52") (name "Net-(L6-Pad2)") (class "Default")
      (node (ref "L6") (pin "2") (pinfunction "2_2") (pintype "unspecified"))
      (node (ref "R1") (pin "2") (pinfunction "2_2") (pintype "input"))
      (node (ref "R18") (pin "1") (pinfunction "1_1") (pintype "input"))
    )
    (net (code "53") (name "Net-(LED1-+)") (class "Default")
      (node (ref "LED1") (pin "1") (pinfunction "+_1") (pintype "unspecified"))
      (node (ref "R11") (pin "1") (pinfunction "1_1") (pintype "input"))
    )
    (net (code "54") (name "Net-(U1-GPIO45)") (class "Default")
      (node (ref "R5") (pin "1") (pinfunction "1_1") (pintype "input"))
      (node (ref "U1") (pin "51") (pinfunction "GPIO45_51") (pintype "unspecified"))
    )
    (net (code "55") (name "Net-(U1-LNA_IN)") (class "Default")
      (node (ref "R18") (pin "2") (pinfunction "2_2") (pintype "input"))
      (node (ref "U1") (pin "1") (pinfunction "LNA_IN_1") (pintype "unspecified"))
    )
    (net (code "56") (name "Net-(U1-U0TXD)") (class "Default")
      (node (ref "R6") (pin "1") (pinfunction "1_1") (pintype "unspecified"))
      (node (ref "U1") (pin "49") (pinfunction "U0TXD_49") (pintype "unspecified"))
    )
    (net (code "57") (name "Net-(U1-XTAL_N)") (class "Default")
      (node (ref "C11") (pin "2") (pinfunction "2_2") (pintype "input"))
      (node (ref "U1") (pin "53") (pinfunction "XTAL_N_53") (pintype "unspecified"))
      (node (ref "X1") (pin "3") (pinfunction "3_3") (pintype "input"))
    )
    (net (code "58") (name "Net-(U1-XTAL_P)") (class "Default")
      (node (ref "L3") (pin "1") (pinfunction "1_1") (pintype "unspecified"))
      (node (ref "U1") (pin "54") (pinfunction "XTAL_P_54") (pintype "unspecified"))
    )
    (net (code "59") (name "Net-(U6-K)") (class "Default")
      (node (ref "U6") (pin "1") (pinfunction "K_1") (pintype "unspecified"))
      (node (ref "U7") (pin "2") (pinfunction "A_2") (pintype "unspecified"))
    )
    (net (code "60") (name "Net-(U7-K)") (class "Default")
      (node (ref "U7") (pin "1") (pinfunction "K_1") (pintype "unspecified"))
      (node (ref "U8") (pin "2") (pinfunction "A_2") (pintype "unspecified"))
    )
    (net (code "61") (name "Net-(U9-BOOT)") (class "Default")
      (node (ref "C22") (pin "2") (pinfunction "2_2") (pintype "unspecified"))
      (node (ref "U9") (pin "1") (pinfunction "BOOT_1") (pintype "unspecified"))
    )
    (net (code "62") (name "Net-(U9-EN)") (class "Default")
      (node (ref "R13") (pin "1") (pinfunction "1_1") (pintype "unspecified"))
      (node (ref "U9") (pin "4") (pinfunction "EN_4") (pintype "unspecified"))
    )
    (net (code "63") (name "Net-(U9-FB)") (class "Default")
      (node (ref "R12") (pin "1") (pinfunction "1_1") (pintype "input"))
      (node (ref "R14") (pin "2") (pinfunction "2_2") (pintype "unspecified"))
      (node (ref "U9") (pin "3") (pinfunction "FB_3") (pintype "unspecified"))
    )
    (net (code "64") (name "Net-(U9-SW)") (class "Default")
      (node (ref "C22") (pin "1") (pinfunction "1_1") (pintype "unspecified"))
      (node (ref "L5") (pin "1") (pinfunction "1_1") (pintype "unspecified"))
      (node (ref "U9") (pin "6") (pinfunction "SW_6") (pintype "unspecified"))
    )
    (net (code "65") (name "Net-(U10-A)") (class "Default")
      (node (ref "U10") (pin "2") (pinfunction "A_2") (pintype "unspecified"))
      (node (ref "U8") (pin "1") (pinfunction "K_1") (pintype "unspecified"))
    )
    (net (code "66") (name "Net-(USB1-CC1)") (class "Default")
      (node (ref "R10") (pin "2") (pinfunction "2_2") (pintype "input"))
      (node (ref "USB1") (pin "4") (pinfunction "CC1_4") (pintype "unspecified"))
    )
    (net (code "67") (name "Net-(USB1-CC2)") (class "Default")
      (node (ref "R7") (pin "2") (pinfunction "2_2") (pintype "input"))
      (node (ref "USB1") (pin "10") (pinfunction "CC2_10") (pintype "unspecified"))
    )
    (net (code "68") (name "VDD3P3") (class "Default")
      (node (ref "C9") (pin "2") (pinfunction "2_2") (pintype "unspecified"))
      (node (ref "L2") (pin "2") (pinfunction "2_2") (pintype "unspecified"))
      (node (ref "U1") (pin "2") (pinfunction "VDD3P3_2") (pintype "unspecified"))
      (node (ref "U1") (pin "3") (pinfunction "VDD3P3_3") (pintype "unspecified"))
    )
    (net (code "69") (name "VDD_SPI") (class "Default")
      (node (ref "C20") (pin "2") (pinfunction "2_2") (pintype "unspecified"))
      (node (ref "C21") (pin "2") (pinfunction "2_2") (pintype "unspecified"))
      (node (ref "U1") (pin "29") (pinfunction "VDD_SPI_29") (pintype "unspecified"))
      (node (ref "U4") (pin "8") (pinfunction "VCC_8") (pintype "unspecified"))
    )
    (net (code "70") (name "unconnected-(ANT1-NC-Pad2)") (class "Default")
      (node (ref "ANT1") (pin "2") (pinfunction "NC_2") (pintype "input+no_connect"))
    )
    (net (code "71") (name "unconnected-(FPC1-Pad1)") (class "Default")
      (node (ref "FPC1") (pin "1") (pinfunction "1_1") (pintype "unspecified+no_connect"))
    )
    (net (code "72") (name "unconnected-(FPC1-Pad23)") (class "Default")
      (node (ref "FPC1") (pin "23") (pinfunction "23_23") (pintype "unspecified+no_connect"))
    )
    (net (code "73") (name "unconnected-(FPC1-Pad24)") (class "Default")
      (node (ref "FPC1") (pin "24") (pinfunction "24_24") (pintype "unspecified+no_connect"))
    )
    (net (code "74") (name "unconnected-(U1-GPIO33-Pad38)") (class "Default")
      (node (ref "U1") (pin "38") (pinfunction "GPIO33_38") (pintype "unspecified+no_connect"))
    )
    (net (code "75") (name "unconnected-(U1-GPIO34-Pad39)") (class "Default")
      (node (ref "U1") (pin "39") (pinfunction "GPIO34_39") (pintype "unspecified+no_connect"))
    )
    (net (code "76") (name "unconnected-(U1-GPIO35-Pad40)") (class "Default")
      (node (ref "U1") (pin "40") (pinfunction "GPIO35_40") (pintype "unspecified+no_connect"))
    )
    (net (code "77") (name "unconnected-(U1-GPIO36-Pad41)") (class "Default")
      (node (ref "U1") (pin "41") (pinfunction "GPIO36_41") (pintype "unspecified+no_connect"))
    )
    (net (code "78") (name "unconnected-(U1-GPIO37-Pad42)") (class "Default")
      (node (ref "U1") (pin "42") (pinfunction "GPIO37_42") (pintype "unspecified+no_connect"))
    )
    (net (code "79") (name "unconnected-(U1-GPIO46-Pad52)") (class "Default")
      (node (ref "U1") (pin "52") (pinfunction "GPIO46_52") (pintype "unspecified+no_connect"))
    )
    (net (code "80") (name "unconnected-(U1-MTDI-Pad47)") (class "Default")
      (node (ref "U1") (pin "47") (pinfunction "MTDI_47") (pintype "unspecified+no_connect"))
    )
    (net (code "81") (name "unconnected-(U1-MTMS-Pad48)") (class "Default")
      (node (ref "U1") (pin "48") (pinfunction "MTMS_48") (pintype "unspecified+no_connect"))
    )
    (net (code "82") (name "unconnected-(U1-SPICLK_P-Pad37)") (class "Default")
      (node (ref "U1") (pin "37") (pinfunction "SPICLK_P_37") (pintype "unspecified+no_connect"))
    )
    (net (code "83") (name "unconnected-(U1-SPICS1-Pad28)") (class "Default")
      (node (ref "U1") (pin "28") (pinfunction "SPICS1_28") (pintype "unspecified+no_connect"))
    )
    (net (code "84") (name "unconnected-(USB1-SBU1-Pad9)") (class "Default")
      (node (ref "USB1") (pin "9") (pinfunction "SBU1_9") (pintype "unspecified+no_connect"))
    )
    (net (code "85") (name "unconnected-(USB1-SBU2-Pad3)") (class "Default")
      (node (ref "USB1") (pin "3") (pinfunction "SBU2_3") (pintype "unspecified+no_connect"))
    )
  )
)
